# USB_Host.net
KiCad netlist of a schematic drawn in Altium Designer
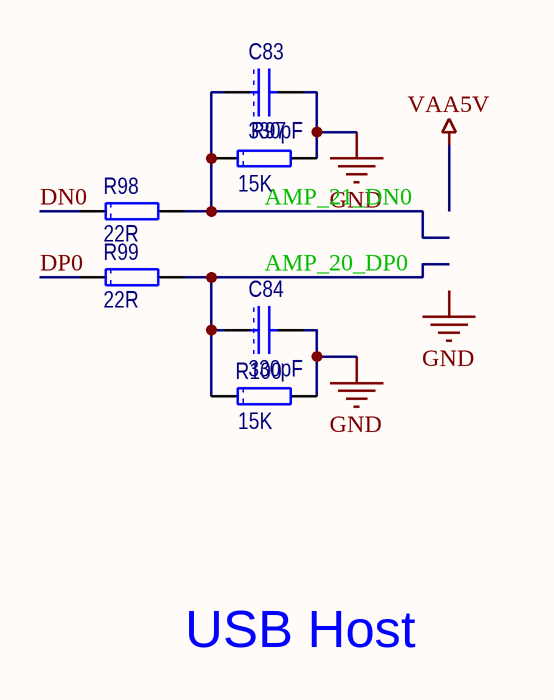
[diagram p0: USB Host.SchDoc]

(export (version "E")
  (design (tool "Eeschema 10.0.6"))
  (components
    (comp (ref "C83")
      (value "330pF")
      (footprint "1608[0603]")
      (description "Capacitor")
      (fields (field (name "MANUFACTURER") "TDK"))
      (libsource (lib "*") (part "CAP"))
    )
    (comp (ref "C84")
      (value "330pF")
      (footprint "1608[0603]")
      (description "Capacitor")
      (fields (field (name "MANUFACTURER") "TDK"))
      (libsource (lib "*") (part "CAP"))
    )
    (comp (ref "R97")
      (value "15K")
      (footprint "1608[0603]R")
      (description "RES")
      (fields (field (name "MANUFACTURER") "vishay"))
      (libsource (lib "*") (part "RES"))
    )
    (comp (ref "R98")
      (value "22R")
      (footprint "1608[0603]R")
      (description "RES")
      (fields (field (name "MANUFACTURER") "vishay"))
      (libsource (lib "*") (part "RES"))
    )
    (comp (ref "R99")
      (value "22R")
      (footprint "1608[0603]R")
      (description "RES")
      (fields (field (name "MANUFACTURER") "vishay"))
      (libsource (lib "*") (part "RES"))
    )
    (comp (ref "R100")
      (value "15K")
      (footprint "1608[0603]R")
      (description "RES")
      (fields (field (name "MANUFACTURER") "vishay"))
      (libsource (lib "*") (part "RES"))
    )
  )
  (nets
    (net (code "1") (name "/AMP_20_DP0") (class "Default")
      (node (ref "C84") (pin "1") (pinfunction "1_1") (pintype "passive"))
      (node (ref "R100") (pin "1") (pinfunction "1_1") (pintype "passive"))
      (node (ref "R99") (pin "2") (pinfunction "2_2") (pintype "passive"))
    )
    (net (code "2") (name "/AMP_21_DN0") (class "Default")
      (node (ref "C83") (pin "1") (pinfunction "1_1") (pintype "passive"))
      (node (ref "R97") (pin "1") (pinfunction "1_1") (pintype "passive"))
      (node (ref "R98") (pin "2") (pinfunction "2_2") (pintype "passive"))
    )
    (net (code "3") (name "/DN0") (class "Default")
      (node (ref "R98") (pin "1") (pinfunction "1_1") (pintype "passive"))
    )
    (net (code "4") (name "/DP0") (class "Default")
      (node (ref "R99") (pin "1") (pinfunction "1_1") (pintype "passive"))
    )
    (net (code "5") (name "GND") (class "Default")
      (node (ref "C83") (pin "2") (pinfunction "2_2") (pintype "passive"))
      (node (ref "C84") (pin "2") (pinfunction "2_2") (pintype "passive"))
      (node (ref "R100") (pin "2") (pinfunction "2_2") (pintype "passive"))
      (node (ref "R97") (pin "2") (pinfunction "2_2") (pintype "passive"))
    )
  )
)
